# SW_PDA_DPNOx5_SMD.net
KiCad netlist of a schematic drawn in Altium Designer
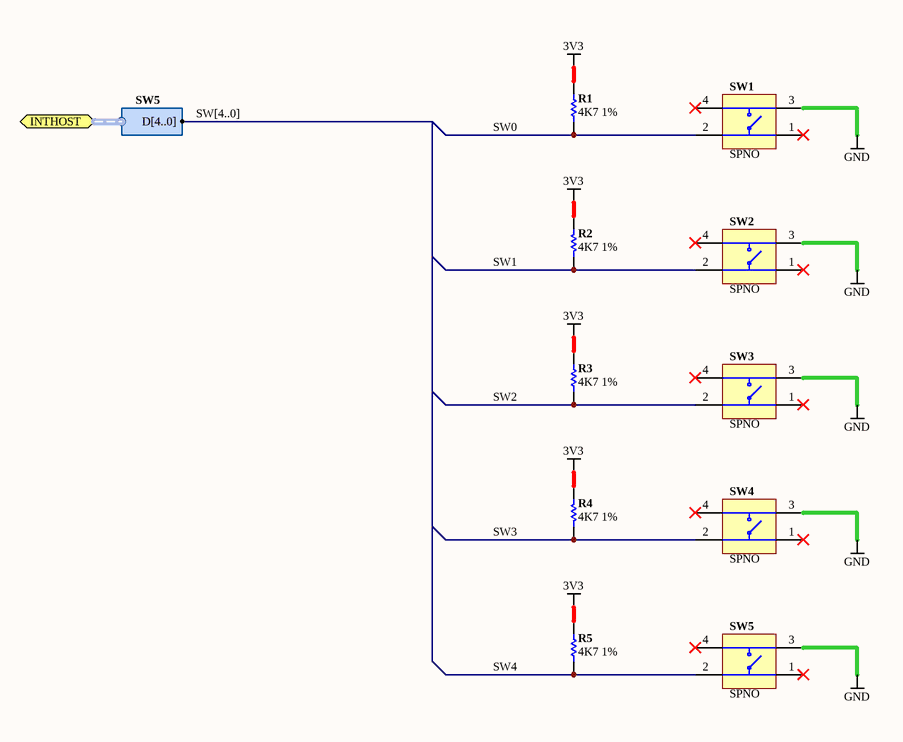
[diagram p0: SW_PDA_DPNOx5_SMD.SCHDOC]

(export (version "E")
  (design (tool "Eeschema 10.0.6"))
  (components
    (comp (ref "R1")
      (value "4K7 1%")
      (footprint "RESC1005-STAR")
      (description "Resistor, 4K7 1% 0402 (1005)")
      (fields (field (name "TOLERANCE") "1 %"))
      (libsource (lib "altium-import") (part "root_0_RES_"))
    )
    (comp (ref "R2")
      (value "4K7 1%")
      (footprint "RESC1005-STAR")
      (description "Resistor, 4K7 1% 0402 (1005)")
      (fields (field (name "TOLERANCE") "1 %"))
      (libsource (lib "altium-import") (part "root_0_mirrored_RES_"))
    )
    (comp (ref "R3")
      (value "4K7 1%")
      (footprint "RESC1005-STAR")
      (description "Resistor, 4K7 1% 0402 (1005)")
      (fields (field (name "TOLERANCE") "1 %"))
      (libsource (lib "altium-import") (part "root_2_RES_"))
    )
    (comp (ref "R4")
      (value "4K7 1%")
      (footprint "RESC1005-STAR")
      (description "Resistor, 4K7 1% 0402 (1005)")
      (fields (field (name "TOLERANCE") "1 %"))
      (libsource (lib "altium-import") (part "root_0_mirrored_RES_"))
    )
    (comp (ref "R5")
      (value "4K7 1%")
      (footprint "RESC1005-STAR")
      (description "Resistor, 4K7 1% 0402 (1005)")
      (fields (field (name "TOLERANCE") "1 %"))
      (libsource (lib "altium-import") (part "root_2_RES_"))
    )
    (comp (ref "SW1")
      (value "SPNO")
      (footprint "SW_DTSM-61NT/R")
      (description "Switch, SPNO Push Button SMD")
      (libsource (lib "AltiumDesignLibrary") (part "SWI-PB-SPNO"))
    )
    (comp (ref "SW2")
      (value "SPNO")
      (footprint "SW_DTSM-61NT/R")
      (description "Switch, SPNO Push Button SMD")
      (libsource (lib "AltiumDesignLibrary") (part "SWI-PB-SPNO"))
    )
    (comp (ref "SW3")
      (value "SPNO")
      (footprint "SW_DTSM-61NT/R")
      (description "Switch, SPNO Push Button SMD")
      (libsource (lib "AltiumDesignLibrary") (part "SWI-PB-SPNO"))
    )
    (comp (ref "SW4")
      (value "SPNO")
      (footprint "SW_DTSM-61NT/R")
      (description "Switch, SPNO Push Button SMD")
      (libsource (lib "AltiumDesignLibrary") (part "SWI-PB-SPNO"))
    )
    (comp (ref "SW5")
      (value "SPNO")
      (footprint "SW_DTSM-61NT/R")
      (description "Switch, SPNO Push Button SMD")
      (libsource (lib "AltiumDesignLibrary") (part "SWI-PB-SPNO"))
    )
  )
  (nets
    (net (code "2") (name "/SW0") (class "Default")
      (node (ref "R1") (pin "2") (pinfunction "2_2") (pintype "passive"))
      (node (ref "SW1") (pin "2") (pinfunction "2_2") (pintype "passive"))
    )
    (net (code "3") (name "/SW1") (class "Default")
      (node (ref "R2") (pin "2") (pinfunction "2_2") (pintype "passive"))
      (node (ref "SW2") (pin "2") (pinfunction "2_2") (pintype "passive"))
    )
    (net (code "4") (name "/SW2") (class "Default")
      (node (ref "R3") (pin "1") (pinfunction "1_1") (pintype "passive"))
      (node (ref "SW3") (pin "2") (pinfunction "2_2") (pintype "passive"))
    )
    (net (code "5") (name "/SW3") (class "Default")
      (node (ref "R4") (pin "2") (pinfunction "2_2") (pintype "passive"))
      (node (ref "SW4") (pin "2") (pinfunction "2_2") (pintype "passive"))
    )
    (net (code "6") (name "/SW4") (class "Default")
      (node (ref "R5") (pin "1") (pinfunction "1_1") (pintype "passive"))
      (node (ref "SW5") (pin "2") (pinfunction "2_2") (pintype "passive"))
    )
    (net (code "9") (name "3V3") (class "Default")
      (node (ref "R1") (pin "1") (pinfunction "1_1") (pintype "passive"))
      (node (ref "R2") (pin "1") (pinfunction "1_1") (pintype "passive"))
      (node (ref "R3") (pin "2") (pinfunction "2_2") (pintype "passive"))
      (node (ref "R4") (pin "1") (pinfunction "1_1") (pintype "passive"))
      (node (ref "R5") (pin "2") (pinfunction "2_2") (pintype "passive"))
    )
    (net (code "10") (name "GND") (class "Default")
      (node (ref "SW1") (pin "3") (pinfunction "3_3") (pintype "passive"))
      (node (ref "SW2") (pin "3") (pinfunction "3_3") (pintype "passive"))
      (node (ref "SW3") (pin "3") (pinfunction "3_3") (pintype "passive"))
      (node (ref "SW4") (pin "3") (pinfunction "3_3") (pintype "passive"))
      (node (ref "SW5") (pin "3") (pinfunction "3_3") (pintype "passive"))
    )
    (net (code "11") (name "unconnected-(SW1-Pad1)") (class "Default")
      (node (ref "SW1") (pin "1") (pinfunction "1_1") (pintype "passive+no_connect"))
    )
    (net (code "12") (name "unconnected-(SW1-Pad4)") (class "Default")
      (node (ref "SW1") (pin "4") (pinfunction "4_4") (pintype "passive+no_connect"))
    )
    (net (code "13") (name "unconnected-(SW2-Pad1)") (class "Default")
      (node (ref "SW2") (pin "1") (pinfunction "1_1") (pintype "passive+no_connect"))
    )
    (net (code "14") (name "unconnected-(SW2-Pad4)") (class "Default")
      (node (ref "SW2") (pin "4") (pinfunction "4_4") (pintype "passive+no_connect"))
    )
    (net (code "15") (name "unconnected-(SW3-Pad1)") (class "Default")
      (node (ref "SW3") (pin "1") (pinfunction "1_1") (pintype "passive+no_connect"))
    )
    (net (code "16") (name "unconnected-(SW3-Pad4)") (class "Default")
      (node (ref "SW3") (pin "4") (pinfunction "4_4") (pintype "passive+no_connect"))
    )
    (net (code "17") (name "unconnected-(SW4-Pad1)") (class "Default")
      (node (ref "SW4") (pin "1") (pinfunction "1_1") (pintype "passive+no_connect"))
    )
    (net (code "18") (name "unconnected-(SW4-Pad4)") (class "Default")
      (node (ref "SW4") (pin "4") (pinfunction "4_4") (pintype "passive+no_connect"))
    )
    (net (code "19") (name "unconnected-(SW5-Pad1)") (class "Default")
      (node (ref "SW5") (pin "1") (pinfunction "1_1") (pintype "passive+no_connect"))
    )
    (net (code "20") (name "unconnected-(SW5-Pad4)") (class "Default")
      (node (ref "SW5") (pin "4") (pinfunction "4_4") (pintype "passive+no_connect"))
    )
  )
)
